# power_ic.net
KiCad netlist of a schematic drawn in Altium Designer
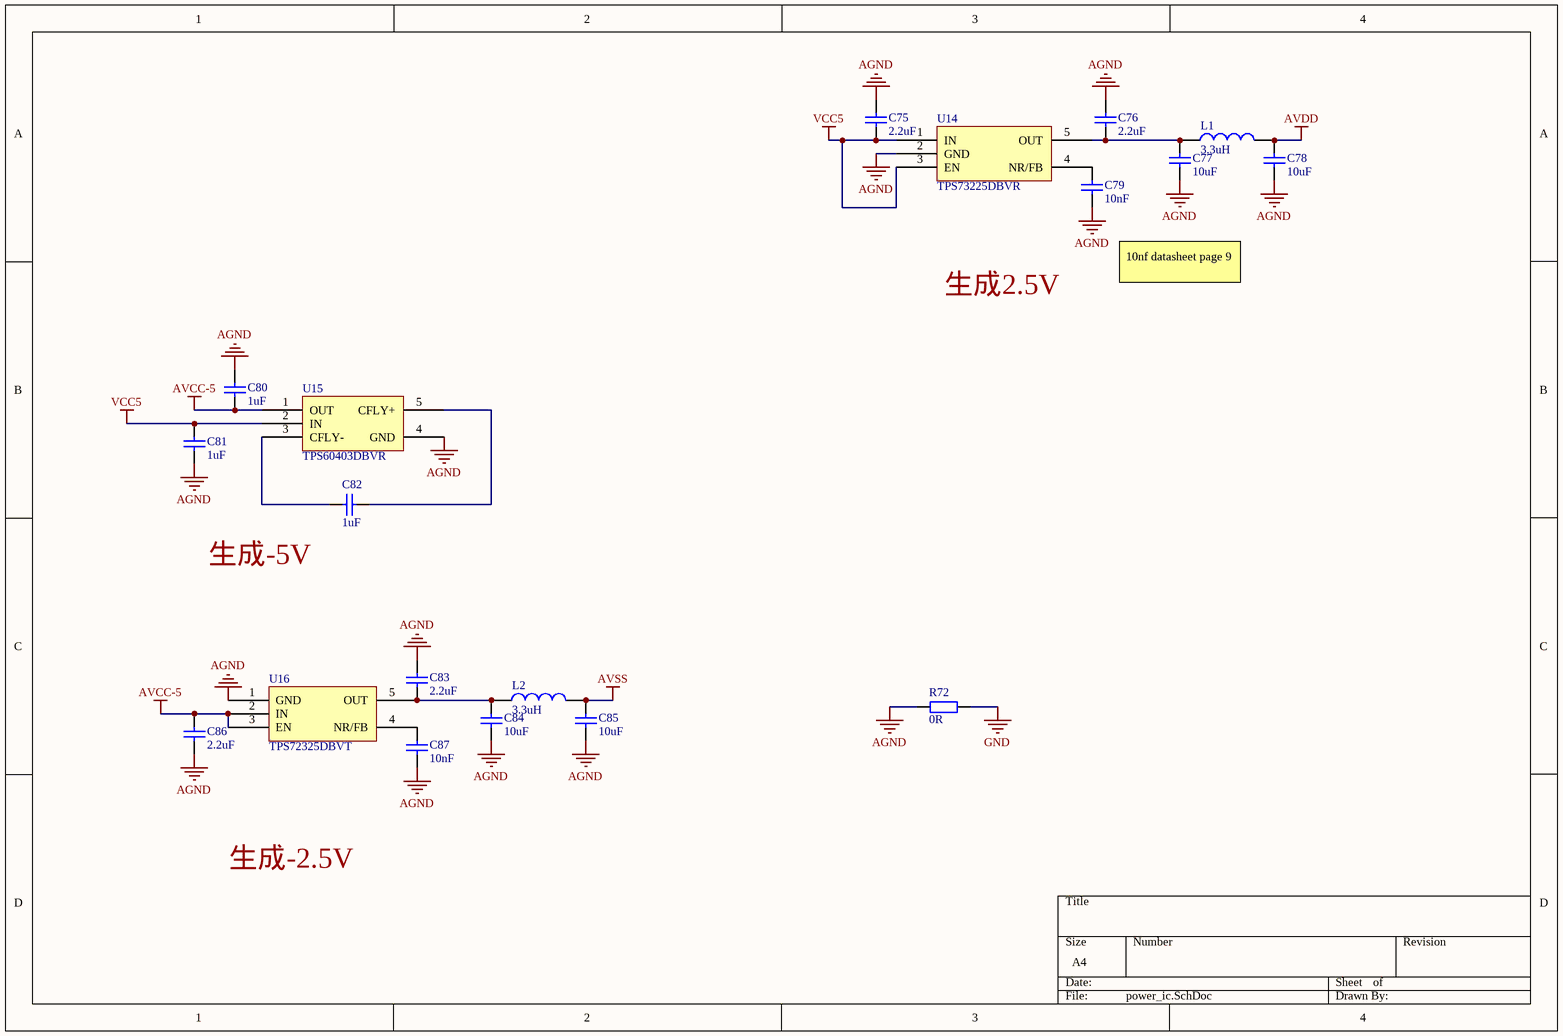
[diagram p0: power_ic.SchDoc]

(export (version "E")
  (design (tool "Eeschema 10.0.6"))
  (components
    (comp (ref "C75")
      (value "2.2uF")
      (footprint "C0603_L")
      (description "贴片电容/MLCC电容")
      (libsource (lib "0.1 - 电阻-电容-电感-保险丝-晶振-晶体-磁珠-电位器-法拉电容-馈通电容") (part "C"))
    )
    (comp (ref "C76")
      (value "2.2uF")
      (footprint "C0603_L")
      (description "贴片电容/MLCC电容")
      (libsource (lib "0.1 - 电阻-电容-电感-保险丝-晶振-晶体-磁珠-电位器-法拉电容-馈通电容") (part "C"))
    )
    (comp (ref "C77")
      (value "10uF")
      (footprint "C0603_L")
      (description "贴片电容/MLCC电容")
      (libsource (lib "0.1 - 电阻-电容-电感-保险丝-晶振-晶体-磁珠-电位器-法拉电容-馈通电容") (part "C"))
    )
    (comp (ref "C78")
      (value "10uF")
      (footprint "C0603_L")
      (description "贴片电容/MLCC电容")
      (libsource (lib "0.1 - 电阻-电容-电感-保险丝-晶振-晶体-磁珠-电位器-法拉电容-馈通电容") (part "C"))
    )
    (comp (ref "C79")
      (value "10nF")
      (footprint "C0603_L")
      (description "贴片电容/MLCC电容")
      (libsource (lib "0.1 - 电阻-电容-电感-保险丝-晶振-晶体-磁珠-电位器-法拉电容-馈通电容") (part "C"))
    )
    (comp (ref "C80")
      (value "1uF")
      (footprint "C0603_L")
      (description "贴片电容/MLCC电容")
      (libsource (lib "0.1 - 电阻-电容-电感-保险丝-晶振-晶体-磁珠-电位器-法拉电容-馈通电容") (part "C"))
    )
    (comp (ref "C81")
      (value "1uF")
      (footprint "C0603_L")
      (description "贴片电容/MLCC电容")
      (libsource (lib "0.1 - 电阻-电容-电感-保险丝-晶振-晶体-磁珠-电位器-法拉电容-馈通电容") (part "C"))
    )
    (comp (ref "C82")
      (value "1uF")
      (footprint "C0603_L")
      (description "贴片电容/MLCC电容")
      (libsource (lib "0.1 - 电阻-电容-电感-保险丝-晶振-晶体-磁珠-电位器-法拉电容-馈通电容") (part "C"))
    )
    (comp (ref "C83")
      (value "2.2uF")
      (footprint "C0603_L")
      (description "贴片电容/MLCC电容")
      (libsource (lib "0.1 - 电阻-电容-电感-保险丝-晶振-晶体-磁珠-电位器-法拉电容-馈通电容") (part "C"))
    )
    (comp (ref "C84")
      (value "10uF")
      (footprint "C0603_L")
      (description "贴片电容/MLCC电容")
      (libsource (lib "0.1 - 电阻-电容-电感-保险丝-晶振-晶体-磁珠-电位器-法拉电容-馈通电容") (part "C"))
    )
    (comp (ref "C85")
      (value "10uF")
      (footprint "C0603_L")
      (description "贴片电容/MLCC电容")
      (libsource (lib "0.1 - 电阻-电容-电感-保险丝-晶振-晶体-磁珠-电位器-法拉电容-馈通电容") (part "C"))
    )
    (comp (ref "C86")
      (value "2.2uF")
      (footprint "C0603_L")
      (description "贴片电容/MLCC电容")
      (libsource (lib "0.1 - 电阻-电容-电感-保险丝-晶振-晶体-磁珠-电位器-法拉电容-馈通电容") (part "C"))
    )
    (comp (ref "C87")
      (value "10nF")
      (footprint "C0603_L")
      (description "贴片电容/MLCC电容")
      (libsource (lib "0.1 - 电阻-电容-电感-保险丝-晶振-晶体-磁珠-电位器-法拉电容-馈通电容") (part "C"))
    )
    (comp (ref "L1")
      (value "3.3uH")
      (footprint "L0805")
      (description "贴片小功率电感")
      (libsource (lib "0.1 - 电阻-电容-电感-保险丝-晶振-晶体-磁珠-电位器-法拉电容-馈通电容") (part "L"))
    )
    (comp (ref "L2")
      (value "3.3uH")
      (footprint "L0805")
      (description "贴片小功率电感")
      (libsource (lib "0.1 - 电阻-电容-电感-保险丝-晶振-晶体-磁珠-电位器-法拉电容-馈通电容") (part "L"))
    )
    (comp (ref "R72")
      (value "0R")
      (footprint "R1206_L")
      (description "贴片电阻")
      (libsource (lib "0.1 - 电阻-电容-电感-保险丝-晶振-晶体-磁珠-电位器-法拉电容-馈通电容") (part "R"))
    )
    (comp (ref "U14")
      (value "TPS73225DBVR")
      (footprint "SOT23-5")
      (description "2.5V输出LDO 30uVRMS 精度1%")
      (libsource (lib "HT") (part "TPS73225DBVR"))
    )
    (comp (ref "U15")
      (value "TPS60403DBVR")
      (footprint "SOT23-5")
      (description "60mA 充电泵电压反向器 250khz")
      (libsource (lib "HT") (part "TPS60403DBVR"))
    )
    (comp (ref "U16")
      (value "TPS72325DBVT")
      (footprint "SOT23-5")
      (description "200mA 负输出低压降线性稳压器 5-SOT-23 -40 to 125")
      (libsource (lib "HT") (part "TPS72325DBVT"))
    )
  )
  (nets
    (net (code "1") (name "AGND") (class "Default")
      (node (ref "C75") (pin "1") (pinfunction "1_1") (pintype "passive"))
      (node (ref "C76") (pin "1") (pinfunction "1_1") (pintype "passive"))
      (node (ref "C77") (pin "2") (pinfunction "2_2") (pintype "passive"))
      (node (ref "C78") (pin "2") (pinfunction "2_2") (pintype "passive"))
      (node (ref "C79") (pin "2") (pinfunction "2_2") (pintype "passive"))
      (node (ref "C80") (pin "2") (pinfunction "2_2") (pintype "passive"))
      (node (ref "C81") (pin "1") (pinfunction "1_1") (pintype "passive"))
      (node (ref "C83") (pin "1") (pinfunction "1_1") (pintype "passive"))
      (node (ref "C84") (pin "2") (pinfunction "2_2") (pintype "passive"))
      (node (ref "C85") (pin "2") (pinfunction "2_2") (pintype "passive"))
      (node (ref "C86") (pin "1") (pinfunction "1_1") (pintype "passive"))
      (node (ref "C87") (pin "2") (pinfunction "2_2") (pintype "passive"))
      (node (ref "R72") (pin "1") (pinfunction "1_1") (pintype "passive"))
      (node (ref "U14") (pin "2") (pinfunction "GND_2") (pintype "passive"))
      (node (ref "U15") (pin "4") (pinfunction "GND_4") (pintype "passive"))
      (node (ref "U16") (pin "1") (pinfunction "GND_1") (pintype "passive"))
    )
    (net (code "2") (name "AVCC-5") (class "Default")
      (node (ref "C80") (pin "1") (pinfunction "1_1") (pintype "passive"))
      (node (ref "C86") (pin "2") (pinfunction "2_2") (pintype "passive"))
      (node (ref "U15") (pin "1") (pinfunction "OUT_1") (pintype "passive"))
      (node (ref "U16") (pin "2") (pinfunction "IN_2") (pintype "passive"))
      (node (ref "U16") (pin "3") (pinfunction "EN_3") (pintype "passive"))
    )
    (net (code "3") (name "AVDD") (class "Default")
      (node (ref "C78") (pin "1") (pinfunction "1_1") (pintype "passive"))
      (node (ref "L1") (pin "2") (pinfunction "2_2") (pintype "passive"))
    )
    (net (code "4") (name "AVSS") (class "Default")
      (node (ref "C85") (pin "1") (pinfunction "1_1") (pintype "passive"))
      (node (ref "L2") (pin "2") (pinfunction "2_2") (pintype "passive"))
    )
    (net (code "5") (name "GND") (class "Default")
      (node (ref "R72") (pin "2") (pinfunction "2_2") (pintype "passive"))
    )
    (net (code "6") (name "Net-(U14-NR{slash}FB)") (class "Default")
      (node (ref "C79") (pin "1") (pinfunction "1_1") (pintype "passive"))
      (node (ref "U14") (pin "4") (pinfunction "NR/FB_4") (pintype "passive"))
    )
    (net (code "7") (name "Net-(U14-OUT)") (class "Default")
      (node (ref "C76") (pin "2") (pinfunction "2_2") (pintype "passive"))
      (node (ref "C77") (pin "1") (pinfunction "1_1") (pintype "passive"))
      (node (ref "L1") (pin "1") (pinfunction "1_1") (pintype "passive"))
      (node (ref "U14") (pin "5") (pinfunction "OUT_5") (pintype "passive"))
    )
    (net (code "8") (name "Net-(U15-CFLY+)") (class "Default")
      (node (ref "C82") (pin "2") (pinfunction "2_2") (pintype "passive"))
      (node (ref "U15") (pin "5") (pinfunction "CFLY+_5") (pintype "passive"))
    )
    (net (code "9") (name "Net-(U15-CFLY-)") (class "Default")
      (node (ref "C82") (pin "1") (pinfunction "1_1") (pintype "passive"))
      (node (ref "U15") (pin "3") (pinfunction "CFLY-_3") (pintype "passive"))
    )
    (net (code "10") (name "Net-(U16-NR{slash}FB)") (class "Default")
      (node (ref "C87") (pin "1") (pinfunction "1_1") (pintype "passive"))
      (node (ref "U16") (pin "4") (pinfunction "NR/FB_4") (pintype "passive"))
    )
    (net (code "11") (name "Net-(U16-OUT)") (class "Default")
      (node (ref "C83") (pin "2") (pinfunction "2_2") (pintype "passive"))
      (node (ref "C84") (pin "1") (pinfunction "1_1") (pintype "passive"))
      (node (ref "L2") (pin "1") (pinfunction "1_1") (pintype "passive"))
      (node (ref "U16") (pin "5") (pinfunction "OUT_5") (pintype "passive"))
    )
    (net (code "12") (name "VCC5") (class "Default")
      (node (ref "C75") (pin "2") (pinfunction "2_2") (pintype "passive"))
      (node (ref "C81") (pin "2") (pinfunction "2_2") (pintype "passive"))
      (node (ref "U14") (pin "1") (pinfunction "IN_1") (pintype "passive"))
      (node (ref "U14") (pin "3") (pinfunction "EN_3") (pintype "passive"))
      (node (ref "U15") (pin "2") (pinfunction "IN_2") (pintype "passive"))
    )
  )
)
